# ETH.net
KiCad netlist of a schematic drawn in Altium Designer
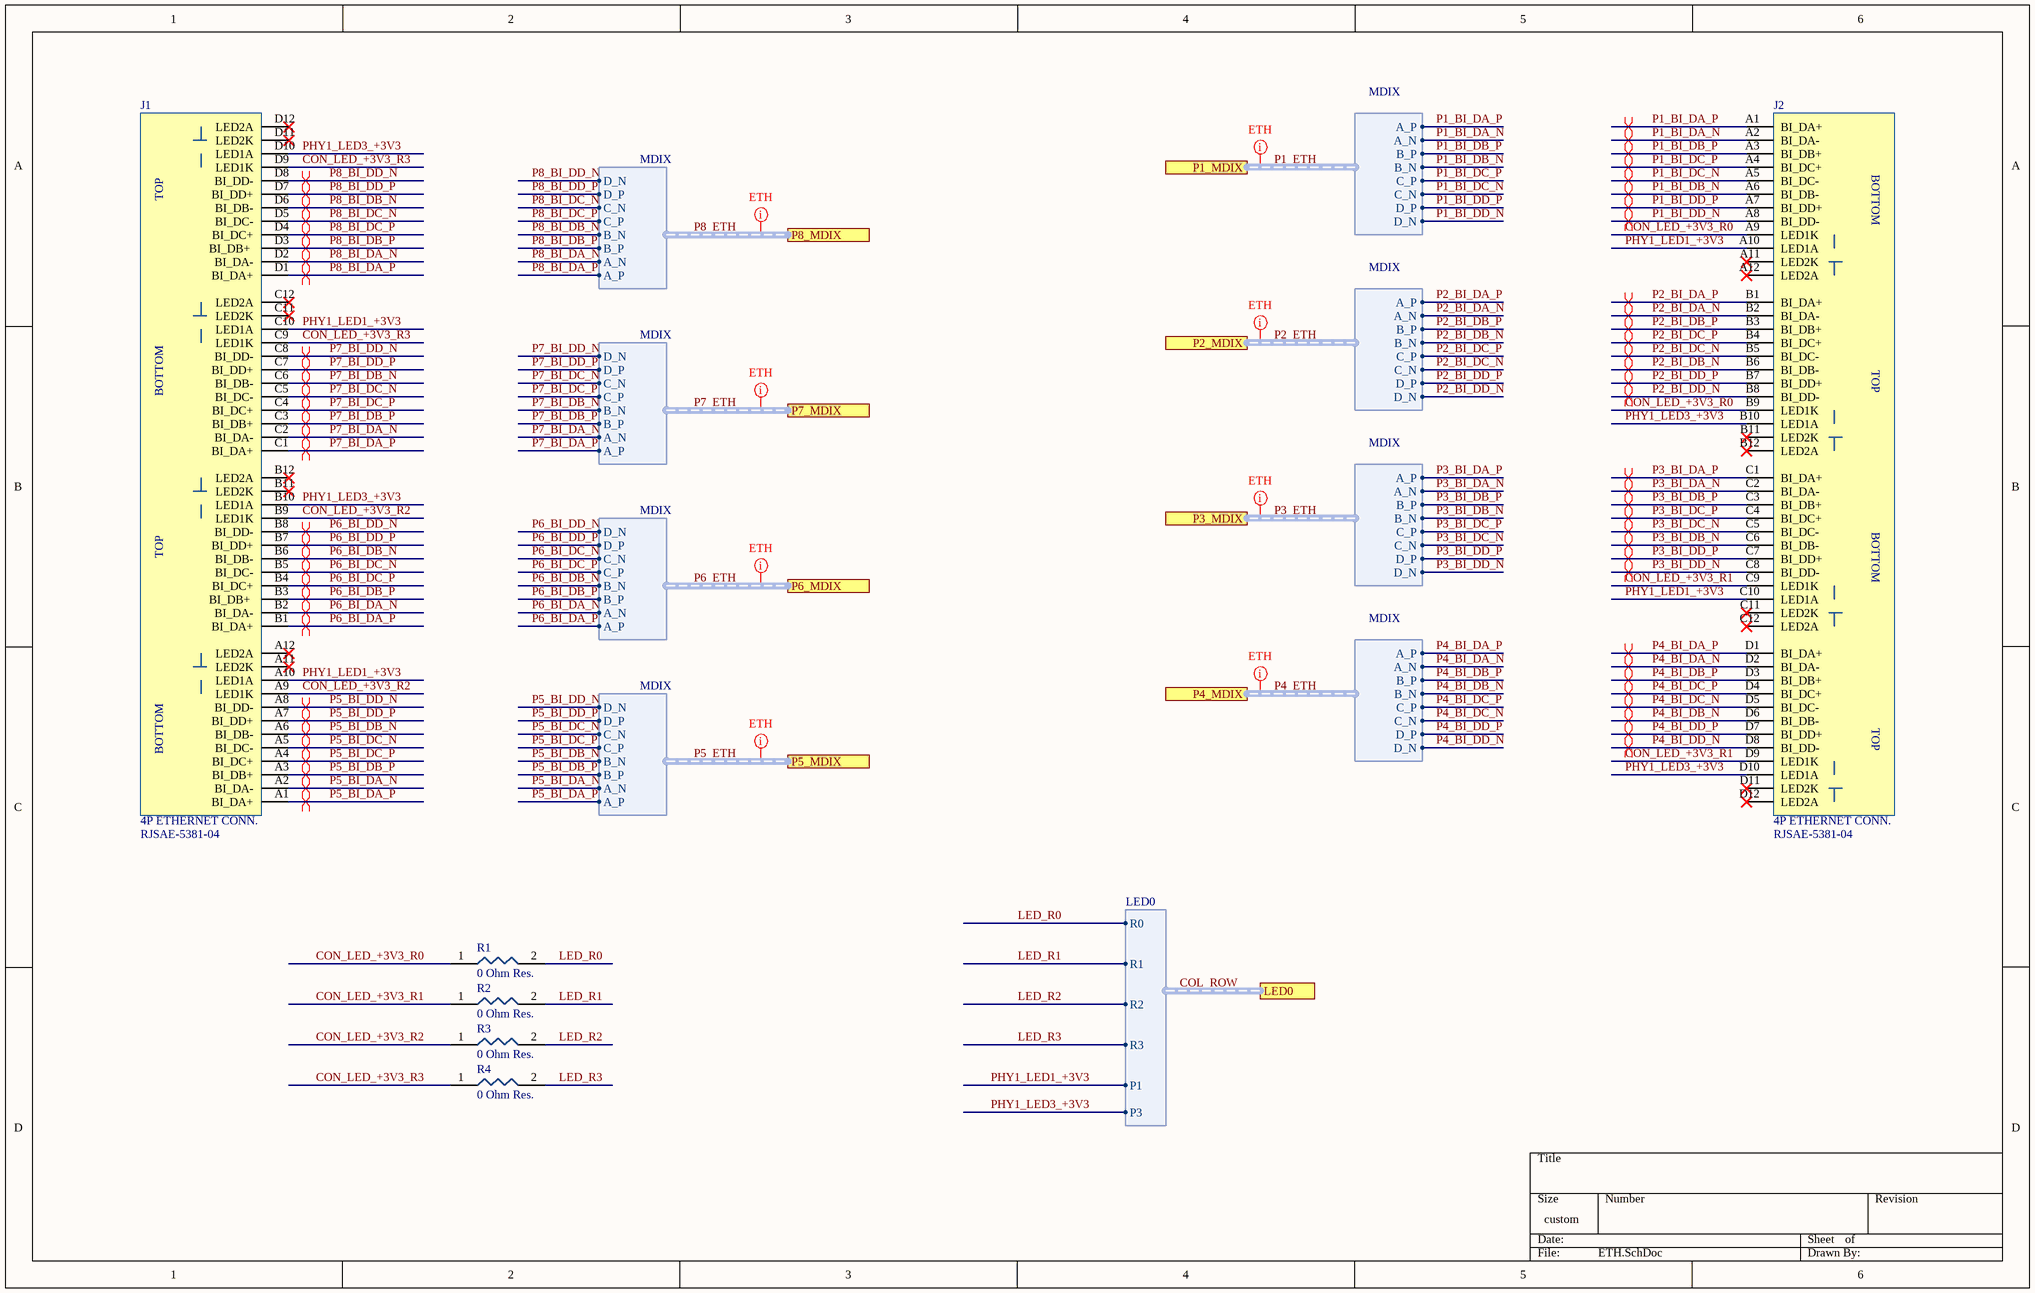
[diagram p0: ETH.SchDoc]

(export (version "E")
  (design (tool "Eeschema 10.0.6"))
  (components
    (comp (ref "J1")
      (value "4P ETHERNET CONN.")
      (footprint "4P Ethernet CONN.")
      (fields (field (name "MANUFACTURER") "Amphenol ICC") (field (name "ORDER NUMBER") "RJSAE-5381-04"))
      (libsource (lib "MyLib") (part "4P ETHERNET CONN."))
    )
    (comp (ref "J2")
      (value "4P ETHERNET CONN.")
      (footprint "4P Ethernet CONN.")
      (fields (field (name "MANUFACTURER") "Amphenol ICC") (field (name "ORDER NUMBER") "RJSAE-5381-04"))
      (libsource (lib "") (part "4P ETHERNET CONN._1"))
    )
    (comp (ref "R1")
      (value "0 Ohm Res.")
      (footprint "0 Ohm Res.")
      (description "0 Ohm Resistor")
      (fields (field (name "MANUFACTURER") "Panasonic"))
      (libsource (lib "MyLib") (part "0 Ohm Res."))
    )
    (comp (ref "R2")
      (value "0 Ohm Res.")
      (footprint "0 Ohm Res.")
      (description "0 Ohm Resistor")
      (fields (field (name "MANUFACTURER") "Panasonic"))
      (libsource (lib "MyLib") (part "0 Ohm Res."))
    )
    (comp (ref "R3")
      (value "0 Ohm Res.")
      (footprint "0 Ohm Res.")
      (description "0 Ohm Resistor")
      (fields (field (name "MANUFACTURER") "Panasonic"))
      (libsource (lib "MyLib") (part "0 Ohm Res."))
    )
    (comp (ref "R4")
      (value "0 Ohm Res.")
      (footprint "0 Ohm Res.")
      (description "0 Ohm Resistor")
      (fields (field (name "MANUFACTURER") "Panasonic"))
      (libsource (lib "MyLib") (part "0 Ohm Res."))
    )
  )
  (nets
    (net (code "11") (name "/CON_LED_+3V3_R0") (class "Default")
      (node (ref "J2") (pin "A9") (pinfunction "LED1K_A9") (pintype "passive"))
      (node (ref "J2") (pin "B9") (pinfunction "LED1K_B9") (pintype "passive"))
      (node (ref "R1") (pin "1") (pinfunction "1_1") (pintype "passive"))
    )
    (net (code "12") (name "/CON_LED_+3V3_R1") (class "Default")
      (node (ref "J2") (pin "C9") (pinfunction "LED1K_C9") (pintype "passive"))
      (node (ref "J2") (pin "D9") (pinfunction "LED1K_D9") (pintype "passive"))
      (node (ref "R2") (pin "1") (pinfunction "1_1") (pintype "passive"))
    )
    (net (code "13") (name "/CON_LED_+3V3_R2") (class "Default")
      (node (ref "J1") (pin "A9") (pinfunction "LED1K_A9") (pintype "passive"))
      (node (ref "J1") (pin "B9") (pinfunction "LED1K_B9") (pintype "passive"))
      (node (ref "R3") (pin "1") (pinfunction "1_1") (pintype "passive"))
    )
    (net (code "14") (name "/CON_LED_+3V3_R3") (class "Default")
      (node (ref "J1") (pin "C9") (pinfunction "LED1K_C9") (pintype "passive"))
      (node (ref "J1") (pin "D9") (pinfunction "LED1K_D9") (pintype "passive"))
      (node (ref "R4") (pin "1") (pinfunction "1_1") (pintype "passive"))
    )
    (net (code "15") (name "/LED_R0") (class "Default")
      (node (ref "R1") (pin "2") (pinfunction "2_2") (pintype "passive"))
    )
    (net (code "16") (name "/LED_R1") (class "Default")
      (node (ref "R2") (pin "2") (pinfunction "2_2") (pintype "passive"))
    )
    (net (code "17") (name "/LED_R2") (class "Default")
      (node (ref "R3") (pin "2") (pinfunction "2_2") (pintype "passive"))
    )
    (net (code "18") (name "/LED_R3") (class "Default")
      (node (ref "R4") (pin "2") (pinfunction "2_2") (pintype "passive"))
    )
    (net (code "19") (name "/P1_BI_DA_N") (class "Default")
      (node (ref "J2") (pin "A2") (pinfunction "BI_DA-_A2") (pintype "passive"))
    )
    (net (code "20") (name "/P1_BI_DA_P") (class "Default")
      (node (ref "J2") (pin "A1") (pinfunction "BI_DA+_A1") (pintype "passive"))
    )
    (net (code "21") (name "/P1_BI_DB_N") (class "Default")
      (node (ref "J2") (pin "A6") (pinfunction "BI_DB-_A6") (pintype "passive"))
    )
    (net (code "22") (name "/P1_BI_DB_P") (class "Default")
      (node (ref "J2") (pin "A3") (pinfunction "BI_DB+_A3") (pintype "passive"))
    )
    (net (code "23") (name "/P1_BI_DC_N") (class "Default")
      (node (ref "J2") (pin "A5") (pinfunction "BI_DC-_A5") (pintype "passive"))
    )
    (net (code "24") (name "/P1_BI_DC_P") (class "Default")
      (node (ref "J2") (pin "A4") (pinfunction "BI_DC+_A4") (pintype "passive"))
    )
    (net (code "25") (name "/P1_BI_DD_N") (class "Default")
      (node (ref "J2") (pin "A8") (pinfunction "BI_DD-_A8") (pintype "passive"))
    )
    (net (code "26") (name "/P1_BI_DD_P") (class "Default")
      (node (ref "J2") (pin "A7") (pinfunction "BI_DD+_A7") (pintype "passive"))
    )
    (net (code "28") (name "/P2_BI_DA_N") (class "Default")
      (node (ref "J2") (pin "B2") (pinfunction "BI_DA-_B2") (pintype "passive"))
    )
    (net (code "29") (name "/P2_BI_DA_P") (class "Default")
      (node (ref "J2") (pin "B1") (pinfunction "BI_DA+_B1") (pintype "passive"))
    )
    (net (code "30") (name "/P2_BI_DB_N") (class "Default")
      (node (ref "J2") (pin "B6") (pinfunction "BI_DB-_B6") (pintype "passive"))
    )
    (net (code "31") (name "/P2_BI_DB_P") (class "Default")
      (node (ref "J2") (pin "B3") (pinfunction "BI_DB+_B3") (pintype "passive"))
    )
    (net (code "32") (name "/P2_BI_DC_N") (class "Default")
      (node (ref "J2") (pin "B5") (pinfunction "BI_DC-_B5") (pintype "passive"))
    )
    (net (code "33") (name "/P2_BI_DC_P") (class "Default")
      (node (ref "J2") (pin "B4") (pinfunction "BI_DC+_B4") (pintype "passive"))
    )
    (net (code "34") (name "/P2_BI_DD_N") (class "Default")
      (node (ref "J2") (pin "B8") (pinfunction "BI_DD-_B8") (pintype "passive"))
    )
    (net (code "35") (name "/P2_BI_DD_P") (class "Default")
      (node (ref "J2") (pin "B7") (pinfunction "BI_DD+_B7") (pintype "passive"))
    )
    (net (code "37") (name "/P3_BI_DA_N") (class "Default")
      (node (ref "J2") (pin "C2") (pinfunction "BI_DA-_C2") (pintype "passive"))
    )
    (net (code "38") (name "/P3_BI_DA_P") (class "Default")
      (node (ref "J2") (pin "C1") (pinfunction "BI_DA+_C1") (pintype "passive"))
    )
    (net (code "39") (name "/P3_BI_DB_N") (class "Default")
      (node (ref "J2") (pin "C6") (pinfunction "BI_DB-_C6") (pintype "passive"))
    )
    (net (code "40") (name "/P3_BI_DB_P") (class "Default")
      (node (ref "J2") (pin "C3") (pinfunction "BI_DB+_C3") (pintype "passive"))
    )
    (net (code "41") (name "/P3_BI_DC_N") (class "Default")
      (node (ref "J2") (pin "C5") (pinfunction "BI_DC-_C5") (pintype "passive"))
    )
    (net (code "42") (name "/P3_BI_DC_P") (class "Default")
      (node (ref "J2") (pin "C4") (pinfunction "BI_DC+_C4") (pintype "passive"))
    )
    (net (code "43") (name "/P3_BI_DD_N") (class "Default")
      (node (ref "J2") (pin "C8") (pinfunction "BI_DD-_C8") (pintype "passive"))
    )
    (net (code "44") (name "/P3_BI_DD_P") (class "Default")
      (node (ref "J2") (pin "C7") (pinfunction "BI_DD+_C7") (pintype "passive"))
    )
    (net (code "46") (name "/P4_BI_DA_N") (class "Default")
      (node (ref "J2") (pin "D2") (pinfunction "BI_DA-_D2") (pintype "passive"))
    )
    (net (code "47") (name "/P4_BI_DA_P") (class "Default")
      (node (ref "J2") (pin "D1") (pinfunction "BI_DA+_D1") (pintype "passive"))
    )
    (net (code "48") (name "/P4_BI_DB_N") (class "Default")
      (node (ref "J2") (pin "D6") (pinfunction "BI_DB-_D6") (pintype "passive"))
    )
    (net (code "49") (name "/P4_BI_DB_P") (class "Default")
      (node (ref "J2") (pin "D3") (pinfunction "BI_DB+_D3") (pintype "passive"))
    )
    (net (code "50") (name "/P4_BI_DC_N") (class "Default")
      (node (ref "J2") (pin "D5") (pinfunction "BI_DC-_D5") (pintype "passive"))
    )
    (net (code "51") (name "/P4_BI_DC_P") (class "Default")
      (node (ref "J2") (pin "D4") (pinfunction "BI_DC+_D4") (pintype "passive"))
    )
    (net (code "52") (name "/P4_BI_DD_N") (class "Default")
      (node (ref "J2") (pin "D8") (pinfunction "BI_DD-_D8") (pintype "passive"))
    )
    (net (code "53") (name "/P4_BI_DD_P") (class "Default")
      (node (ref "J2") (pin "D7") (pinfunction "BI_DD+_D7") (pintype "passive"))
    )
    (net (code "55") (name "/P5_BI_DA_N") (class "Default")
      (node (ref "J1") (pin "A2") (pinfunction "BI_DA-_A2") (pintype "passive"))
    )
    (net (code "56") (name "/P5_BI_DA_P") (class "Default")
      (node (ref "J1") (pin "A1") (pinfunction "BI_DA+_A1") (pintype "passive"))
    )
    (net (code "57") (name "/P5_BI_DB_N") (class "Default")
      (node (ref "J1") (pin "A6") (pinfunction "BI_DB-_A6") (pintype "passive"))
    )
    (net (code "58") (name "/P5_BI_DB_P") (class "Default")
      (node (ref "J1") (pin "A3") (pinfunction "BI_DB+_A3") (pintype "passive"))
    )
    (net (code "59") (name "/P5_BI_DC_N") (class "Default")
      (node (ref "J1") (pin "A5") (pinfunction "BI_DC-_A5") (pintype "passive"))
    )
    (net (code "60") (name "/P5_BI_DC_P") (class "Default")
      (node (ref "J1") (pin "A4") (pinfunction "BI_DC+_A4") (pintype "passive"))
    )
    (net (code "61") (name "/P5_BI_DD_N") (class "Default")
      (node (ref "J1") (pin "A8") (pinfunction "BI_DD-_A8") (pintype "passive"))
    )
    (net (code "62") (name "/P5_BI_DD_P") (class "Default")
      (node (ref "J1") (pin "A7") (pinfunction "BI_DD+_A7") (pintype "passive"))
    )
    (net (code "64") (name "/P6_BI_DA_N") (class "Default")
      (node (ref "J1") (pin "B2") (pinfunction "BI_DA-_B2") (pintype "passive"))
    )
    (net (code "65") (name "/P6_BI_DA_P") (class "Default")
      (node (ref "J1") (pin "B1") (pinfunction "BI_DA+_B1") (pintype "passive"))
    )
    (net (code "66") (name "/P6_BI_DB_N") (class "Default")
      (node (ref "J1") (pin "B6") (pinfunction "BI_DB-_B6") (pintype "passive"))
    )
    (net (code "67") (name "/P6_BI_DB_P") (class "Default")
      (node (ref "J1") (pin "B3") (pinfunction "BI_DB+_B3") (pintype "passive"))
    )
    (net (code "68") (name "/P6_BI_DC_N") (class "Default")
      (node (ref "J1") (pin "B5") (pinfunction "BI_DC-_B5") (pintype "passive"))
    )
    (net (code "69") (name "/P6_BI_DC_P") (class "Default")
      (node (ref "J1") (pin "B4") (pinfunction "BI_DC+_B4") (pintype "passive"))
    )
    (net (code "70") (name "/P6_BI_DD_N") (class "Default")
      (node (ref "J1") (pin "B8") (pinfunction "BI_DD-_B8") (pintype "passive"))
    )
    (net (code "71") (name "/P6_BI_DD_P") (class "Default")
      (node (ref "J1") (pin "B7") (pinfunction "BI_DD+_B7") (pintype "passive"))
    )
    (net (code "73") (name "/P7_BI_DA_N") (class "Default")
      (node (ref "J1") (pin "C2") (pinfunction "BI_DA-_C2") (pintype "passive"))
    )
    (net (code "74") (name "/P7_BI_DA_P") (class "Default")
      (node (ref "J1") (pin "C1") (pinfunction "BI_DA+_C1") (pintype "passive"))
    )
    (net (code "75") (name "/P7_BI_DB_N") (class "Default")
      (node (ref "J1") (pin "C6") (pinfunction "BI_DB-_C6") (pintype "passive"))
    )
    (net (code "76") (name "/P7_BI_DB_P") (class "Default")
      (node (ref "J1") (pin "C3") (pinfunction "BI_DB+_C3") (pintype "passive"))
    )
    (net (code "77") (name "/P7_BI_DC_N") (class "Default")
      (node (ref "J1") (pin "C5") (pinfunction "BI_DC-_C5") (pintype "passive"))
    )
    (net (code "78") (name "/P7_BI_DC_P") (class "Default")
      (node (ref "J1") (pin "C4") (pinfunction "BI_DC+_C4") (pintype "passive"))
    )
    (net (code "79") (name "/P7_BI_DD_N") (class "Default")
      (node (ref "J1") (pin "C8") (pinfunction "BI_DD-_C8") (pintype "passive"))
    )
    (net (code "80") (name "/P7_BI_DD_P") (class "Default")
      (node (ref "J1") (pin "C7") (pinfunction "BI_DD+_C7") (pintype "passive"))
    )
    (net (code "82") (name "/P8_BI_DA_N") (class "Default")
      (node (ref "J1") (pin "D2") (pinfunction "BI_DA-_D2") (pintype "passive"))
    )
    (net (code "83") (name "/P8_BI_DA_P") (class "Default")
      (node (ref "J1") (pin "D1") (pinfunction "BI_DA+_D1") (pintype "passive"))
    )
    (net (code "84") (name "/P8_BI_DB_N") (class "Default")
      (node (ref "J1") (pin "D6") (pinfunction "BI_DB-_D6") (pintype "passive"))
    )
    (net (code "85") (name "/P8_BI_DB_P") (class "Default")
      (node (ref "J1") (pin "D3") (pinfunction "BI_DB+_D3") (pintype "passive"))
    )
    (net (code "86") (name "/P8_BI_DC_N") (class "Default")
      (node (ref "J1") (pin "D5") (pinfunction "BI_DC-_D5") (pintype "passive"))
    )
    (net (code "87") (name "/P8_BI_DC_P") (class "Default")
      (node (ref "J1") (pin "D4") (pinfunction "BI_DC+_D4") (pintype "passive"))
    )
    (net (code "88") (name "/P8_BI_DD_N") (class "Default")
      (node (ref "J1") (pin "D8") (pinfunction "BI_DD-_D8") (pintype "passive"))
    )
    (net (code "89") (name "/P8_BI_DD_P") (class "Default")
      (node (ref "J1") (pin "D7") (pinfunction "BI_DD+_D7") (pintype "passive"))
    )
    (net (code "91") (name "/PHY1_LED1_+3V3") (class "Default")
      (node (ref "J1") (pin "A10") (pinfunction "LED1A_A10") (pintype "passive"))
      (node (ref "J1") (pin "C10") (pinfunction "LED1A_C10") (pintype "passive"))
      (node (ref "J2") (pin "A10") (pinfunction "LED1A_A10") (pintype "passive"))
      (node (ref "J2") (pin "C10") (pinfunction "LED1A_C10") (pintype "passive"))
    )
    (net (code "92") (name "/PHY1_LED3_+3V3") (class "Default")
      (node (ref "J1") (pin "B10") (pinfunction "LED1A_B10") (pintype "passive"))
      (node (ref "J1") (pin "D10") (pinfunction "LED1A_D10") (pintype "passive"))
      (node (ref "J2") (pin "B10") (pinfunction "LED1A_B10") (pintype "passive"))
      (node (ref "J2") (pin "D10") (pinfunction "LED1A_D10") (pintype "passive"))
    )
    (net (code "93") (name "unconnected-(J1-LED2A-PadA12)") (class "Default")
      (node (ref "J1") (pin "A12") (pinfunction "LED2A_A12") (pintype "passive+no_connect"))
    )
    (net (code "94") (name "unconnected-(J1-LED2A-PadB12)") (class "Default")
      (node (ref "J1") (pin "B12") (pinfunction "LED2A_B12") (pintype "passive+no_connect"))
    )
    (net (code "95") (name "unconnected-(J1-LED2A-PadC12)") (class "Default")
      (node (ref "J1") (pin "C12") (pinfunction "LED2A_C12") (pintype "passive+no_connect"))
    )
    (net (code "96") (name "unconnected-(J1-LED2A-PadD12)") (class "Default")
      (node (ref "J1") (pin "D12") (pinfunction "LED2A_D12") (pintype "passive+no_connect"))
    )
    (net (code "97") (name "unconnected-(J1-LED2K-PadA11)") (class "Default")
      (node (ref "J1") (pin "A11") (pinfunction "LED2K_A11") (pintype "passive+no_connect"))
    )
    (net (code "98") (name "unconnected-(J1-LED2K-PadB11)") (class "Default")
      (node (ref "J1") (pin "B11") (pinfunction "LED2K_B11") (pintype "passive+no_connect"))
    )
    (net (code "99") (name "unconnected-(J1-LED2K-PadC11)") (class "Default")
      (node (ref "J1") (pin "C11") (pinfunction "LED2K_C11") (pintype "passive+no_connect"))
    )
    (net (code "100") (name "unconnected-(J1-LED2K-PadD11)") (class "Default")
      (node (ref "J1") (pin "D11") (pinfunction "LED2K_D11") (pintype "passive+no_connect"))
    )
    (net (code "101") (name "unconnected-(J2-LED2A-PadA12)") (class "Default")
      (node (ref "J2") (pin "A12") (pinfunction "LED2A_A12") (pintype "passive+no_connect"))
    )
    (net (code "102") (name "unconnected-(J2-LED2A-PadB12)") (class "Default")
      (node (ref "J2") (pin "B12") (pinfunction "LED2A_B12") (pintype "passive+no_connect"))
    )
    (net (code "103") (name "unconnected-(J2-LED2A-PadC12)") (class "Default")
      (node (ref "J2") (pin "C12") (pinfunction "LED2A_C12") (pintype "passive+no_connect"))
    )
    (net (code "104") (name "unconnected-(J2-LED2A-PadD12)") (class "Default")
      (node (ref "J2") (pin "D12") (pinfunction "LED2A_D12") (pintype "passive+no_connect"))
    )
    (net (code "105") (name "unconnected-(J2-LED2K-PadA11)") (class "Default")
      (node (ref "J2") (pin "A11") (pinfunction "LED2K_A11") (pintype "passive+no_connect"))
    )
    (net (code "106") (name "unconnected-(J2-LED2K-PadB11)") (class "Default")
      (node (ref "J2") (pin "B11") (pinfunction "LED2K_B11") (pintype "passive+no_connect"))
    )
    (net (code "107") (name "unconnected-(J2-LED2K-PadC11)") (class "Default")
      (node (ref "J2") (pin "C11") (pinfunction "LED2K_C11") (pintype "passive+no_connect"))
    )
    (net (code "108") (name "unconnected-(J2-LED2K-PadD11)") (class "Default")
      (node (ref "J2") (pin "D11") (pinfunction "LED2K_D11") (pintype "passive+no_connect"))
    )
  )
)
